# rc13-mbed-main-board2.net
KiCad netlist of a schematic drawn in EAGLE
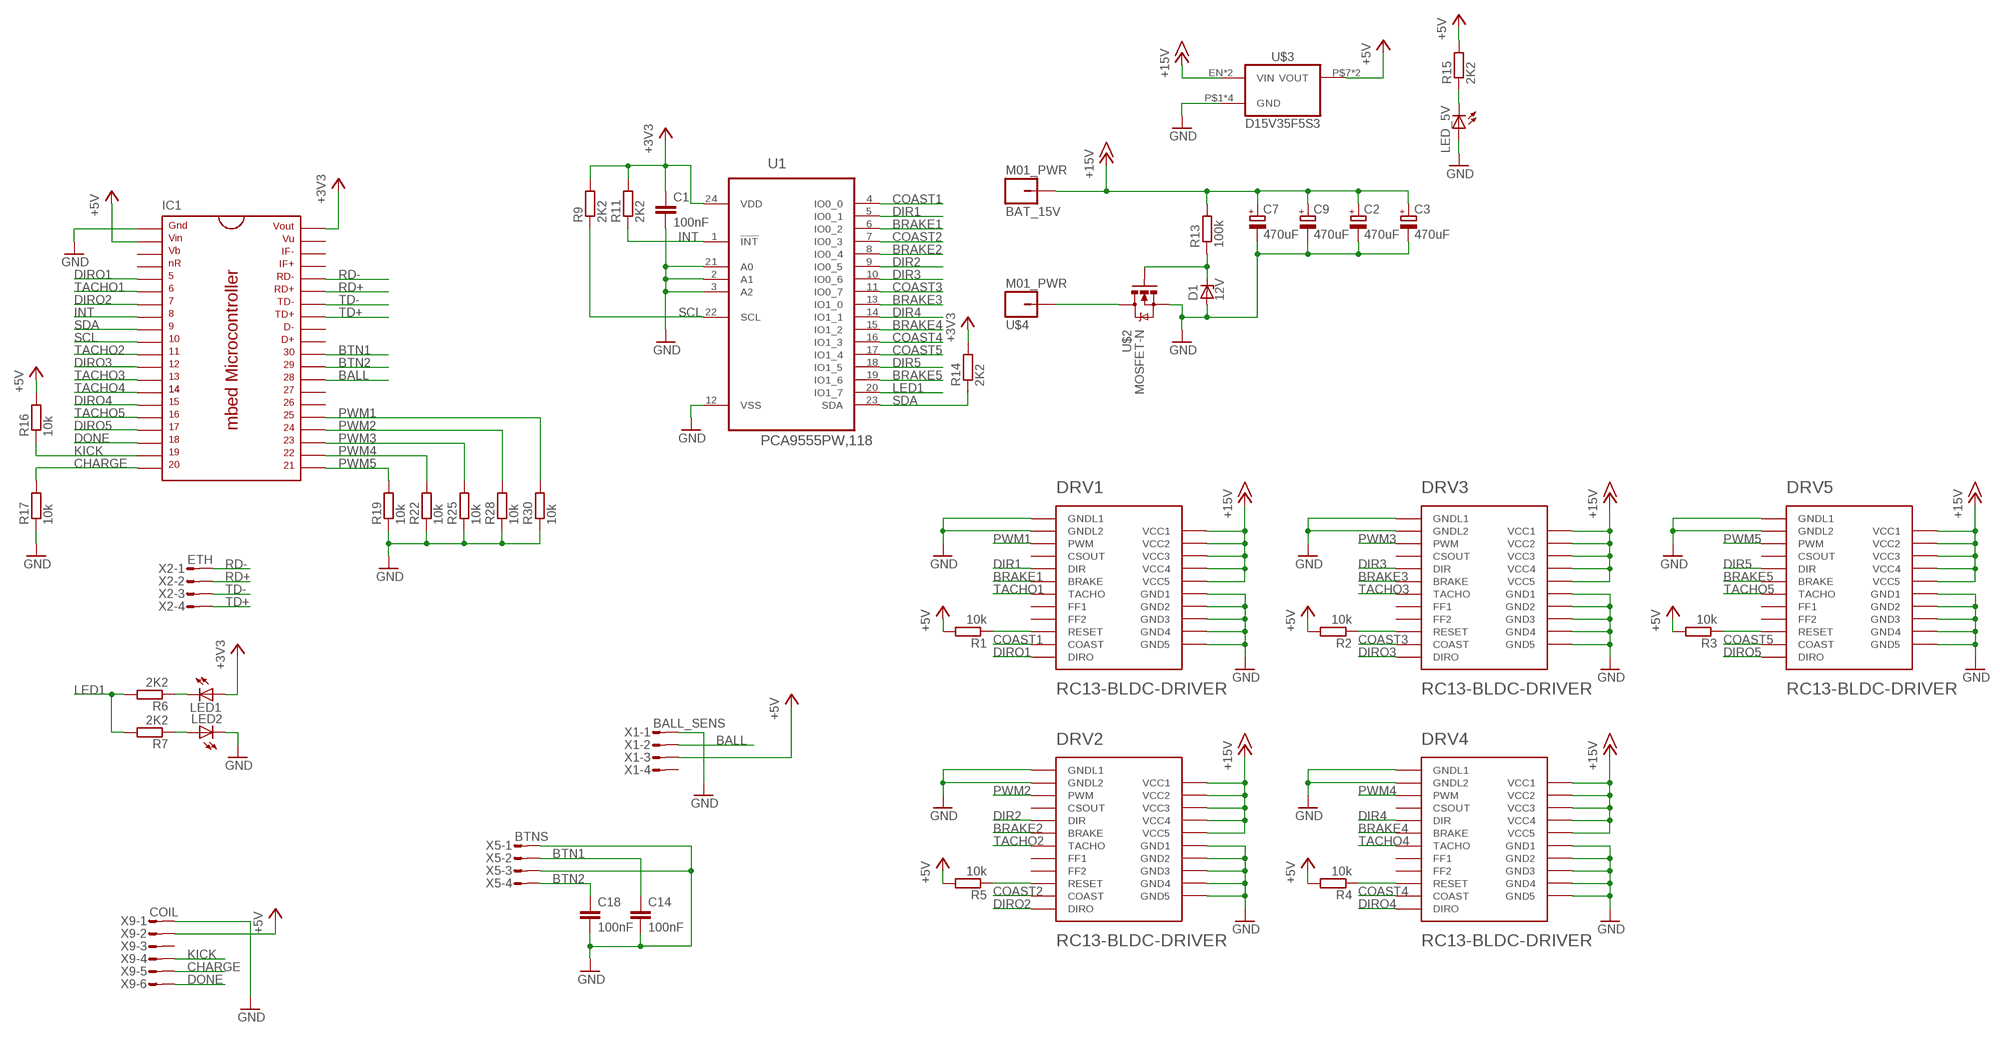
[diagram p0: schematic, sheet 1]

(export (version "E")
  (design (tool "Eeschema 10.0.6"))
  (components
    (comp (ref "BAT_15V")
      (value "M01_PWR")
      (footprint "eagle-import:PWR_HOLE")
      (libsource (lib "eagle-import") (part "M01_PWR"))
    )
    (comp (ref "C1")
      (value "100nF")
      (footprint "eagle-import:C0603K")
      (libsource (lib "eagle-import") (part "C-EUC0603K"))
    )
    (comp (ref "C2")
      (value "470uF")
      (footprint "eagle-import:E3,5-8")
      (libsource (lib "eagle-import") (part "CPOL-EUE3.5-8"))
    )
    (comp (ref "C3")
      (value "470uF")
      (footprint "eagle-import:E3,5-8")
      (libsource (lib "eagle-import") (part "CPOL-EUE3.5-8"))
    )
    (comp (ref "C7")
      (value "470uF")
      (footprint "eagle-import:E3,5-8")
      (libsource (lib "eagle-import") (part "CPOL-EUE3.5-8"))
    )
    (comp (ref "C9")
      (value "470uF")
      (footprint "eagle-import:E3,5-8")
      (libsource (lib "eagle-import") (part "CPOL-EUE3.5-8"))
    )
    (comp (ref "C14")
      (value "100nF")
      (footprint "eagle-import:C0603K")
      (libsource (lib "eagle-import") (part "C-EUC0603K"))
    )
    (comp (ref "C18")
      (value "100nF")
      (footprint "eagle-import:C0603K")
      (libsource (lib "eagle-import") (part "C-EUC0603K"))
    )
    (comp (ref "D1")
      (value "12V")
      (footprint "eagle-import:SOD123")
      (libsource (lib "eagle-import") (part "ZENER-DIODESOD123"))
    )
    (comp (ref "DRV1")
      (value "RC13-BLDC-DRIVER")
      (footprint "eagle-import:RC13-BLDC-DRIVER")
      (libsource (lib "eagle-import") (part "RC13-BLDC-DRIVER"))
    )
    (comp (ref "DRV2")
      (value "RC13-BLDC-DRIVER")
      (footprint "eagle-import:RC13-BLDC-DRIVER")
      (libsource (lib "eagle-import") (part "RC13-BLDC-DRIVER"))
    )
    (comp (ref "DRV3")
      (value "RC13-BLDC-DRIVER")
      (footprint "eagle-import:RC13-BLDC-DRIVER")
      (libsource (lib "eagle-import") (part "RC13-BLDC-DRIVER"))
    )
    (comp (ref "DRV4")
      (value "RC13-BLDC-DRIVER")
      (footprint "eagle-import:RC13-BLDC-DRIVER")
      (libsource (lib "eagle-import") (part "RC13-BLDC-DRIVER"))
    )
    (comp (ref "DRV5")
      (value "RC13-BLDC-DRIVER")
      (footprint "eagle-import:RC13-BLDC-DRIVER")
      (libsource (lib "eagle-import") (part "RC13-BLDC-DRIVER"))
    )
    (comp (ref "IC1")
      (value "MBED_MICROCONTROLLER")
      (footprint "eagle-import:DIL40_0.9")
      (libsource (lib "eagle-import") (part "MBED_MICROCONTROLLER"))
    )
    (comp (ref "LED1")
      (value "LEDCHIP-LED0603")
      (footprint "eagle-import:CHIP-LED0603")
      (libsource (lib "eagle-import") (part "LEDCHIP-LED0603"))
    )
    (comp (ref "LED2")
      (value "LEDCHIP-LED0603")
      (footprint "eagle-import:CHIP-LED0603")
      (libsource (lib "eagle-import") (part "LEDCHIP-LED0603"))
    )
    (comp (ref "LED_5V")
      (value "LEDCHIP-LED0603")
      (footprint "eagle-import:CHIP-LED0603")
      (libsource (lib "eagle-import") (part "LEDCHIP-LED0603"))
    )
    (comp (ref "R1")
      (value "10k")
      (footprint "eagle-import:R0603")
      (libsource (lib "eagle-import") (part "R-EU_R0603"))
    )
    (comp (ref "R2")
      (value "10k")
      (footprint "eagle-import:R0603")
      (libsource (lib "eagle-import") (part "R-EU_R0603"))
    )
    (comp (ref "R3")
      (value "10k")
      (footprint "eagle-import:R0603")
      (libsource (lib "eagle-import") (part "R-EU_R0603"))
    )
    (comp (ref "R4")
      (value "10k")
      (footprint "eagle-import:R0603")
      (libsource (lib "eagle-import") (part "R-EU_R0603"))
    )
    (comp (ref "R5")
      (value "10k")
      (footprint "eagle-import:R0603")
      (libsource (lib "eagle-import") (part "R-EU_R0603"))
    )
    (comp (ref "R6")
      (value "2K2")
      (footprint "eagle-import:R0603")
      (libsource (lib "eagle-import") (part "R-EU_R0603"))
    )
    (comp (ref "R7")
      (value "2K2")
      (footprint "eagle-import:R0603")
      (libsource (lib "eagle-import") (part "R-EU_R0603"))
    )
    (comp (ref "R9")
      (value "2K2")
      (footprint "eagle-import:R0603")
      (libsource (lib "eagle-import") (part "R-EU_R0603"))
    )
    (comp (ref "R11")
      (value "2K2")
      (footprint "eagle-import:R0603")
      (libsource (lib "eagle-import") (part "R-EU_R0603"))
    )
    (comp (ref "R13")
      (value "100k")
      (footprint "eagle-import:R0603")
      (libsource (lib "eagle-import") (part "R-EU_R0603"))
    )
    (comp (ref "R14")
      (value "2K2")
      (footprint "eagle-import:R0603")
      (libsource (lib "eagle-import") (part "R-EU_R0603"))
    )
    (comp (ref "R15")
      (value "2K2")
      (footprint "eagle-import:R0603")
      (libsource (lib "eagle-import") (part "R-EU_R0603"))
    )
    (comp (ref "R16")
      (value "10k")
      (footprint "eagle-import:R0603")
      (libsource (lib "eagle-import") (part "R-EU_R0603"))
    )
    (comp (ref "R17")
      (value "10k")
      (footprint "eagle-import:R0603")
      (libsource (lib "eagle-import") (part "R-EU_R0603"))
    )
    (comp (ref "R19")
      (value "10k")
      (footprint "eagle-import:R0603")
      (libsource (lib "eagle-import") (part "R-EU_R0603"))
    )
    (comp (ref "R22")
      (value "10k")
      (footprint "eagle-import:R0603")
      (libsource (lib "eagle-import") (part "R-EU_R0603"))
    )
    (comp (ref "R25")
      (value "10k")
      (footprint "eagle-import:R0603")
      (libsource (lib "eagle-import") (part "R-EU_R0603"))
    )
    (comp (ref "R28")
      (value "10k")
      (footprint "eagle-import:R0603")
      (libsource (lib "eagle-import") (part "R-EU_R0603"))
    )
    (comp (ref "R30")
      (value "10k")
      (footprint "eagle-import:R0603")
      (libsource (lib "eagle-import") (part "R-EU_R0603"))
    )
    (comp (ref "U$2")
      (value "MOSFET-N")
      (footprint "eagle-import:TO127P600X120-5N")
      (libsource (lib "eagle-import") (part "MOSFET-N-SOT669"))
    )
    (comp (ref "U$3")
      (value "D15V35F5S3")
      (footprint "eagle-import:D15V35F5S3")
      (libsource (lib "eagle-import") (part "D15V35F5S3"))
    )
    (comp (ref "U$4")
      (value "M01_PWR")
      (footprint "eagle-import:PWR_HOLE")
      (libsource (lib "eagle-import") (part "M01_PWR"))
    )
    (comp (ref "U1")
      (value "PCA9555PW,118")
      (footprint "eagle-import:SOP65P640X110-24N")
      (libsource (lib "eagle-import") (part "PCA9555PW,118"))
    )
    (comp (ref "X1")
      (value "BALL_SENS")
      (footprint "eagle-import:MICROMATCH-4")
      (fields (field (name "MPN") "7-215464-4"))
      (libsource (lib "eagle-import") (part "MICROMATCH-4"))
    )
    (comp (ref "X2")
      (value "ETH")
      (footprint "eagle-import:MICROMATCH-4")
      (fields (field (name "MPN") "7-215464-4"))
      (libsource (lib "eagle-import") (part "MICROMATCH-4"))
    )
    (comp (ref "X5")
      (value "BTNS")
      (footprint "eagle-import:MICROMATCH-4")
      (fields (field (name "MPN") "7-215464-4"))
      (libsource (lib "eagle-import") (part "MICROMATCH-4"))
    )
    (comp (ref "X9")
      (value "COIL")
      (footprint "eagle-import:MICROMATCH-6")
      (fields (field (name "MPN") "7-215464-6"))
      (libsource (lib "eagle-import") (part "MICROMATCH-6"))
    )
  )
  (nets
    (net (code "1") (name "+3V3") (class "Default")
      (node (ref "C1") (pin "1") (pinfunction "1_1") (pintype "passive"))
      (node (ref "IC1") (pin "40") (pinfunction "P$40_40") (pintype "bidirectional"))
      (node (ref "LED1") (pin "A") (pinfunction "A_A") (pintype "passive"))
      (node (ref "R11") (pin "2") (pinfunction "2_2") (pintype "passive"))
      (node (ref "R14") (pin "2") (pinfunction "2_2") (pintype "passive"))
      (node (ref "R9") (pin "2") (pinfunction "2_2") (pintype "passive"))
      (node (ref "U1") (pin "24") (pinfunction "VDD_24") (pintype "power_in"))
    )
    (net (code "2") (name "+5V") (class "Default")
      (node (ref "IC1") (pin "2") (pinfunction "P$2_2") (pintype "bidirectional"))
      (node (ref "R1") (pin "2") (pinfunction "2_2") (pintype "passive"))
      (node (ref "R15") (pin "2") (pinfunction "2_2") (pintype "passive"))
      (node (ref "R16") (pin "2") (pinfunction "2_2") (pintype "passive"))
      (node (ref "R2") (pin "2") (pinfunction "2_2") (pintype "passive"))
      (node (ref "R3") (pin "2") (pinfunction "2_2") (pintype "passive"))
      (node (ref "R4") (pin "2") (pinfunction "2_2") (pintype "passive"))
      (node (ref "R5") (pin "2") (pinfunction "2_2") (pintype "passive"))
      (node (ref "U$3") (pin "P$7") (pinfunction "VOUT_P$7") (pintype "power_in"))
      (node (ref "U$3") (pin "P$8") (pinfunction "VOUT_P$8") (pintype "power_in"))
      (node (ref "X1") (pin "3") (pinfunction "S_3") (pintype "passive"))
      (node (ref "X9") (pin "2") (pinfunction "S_2") (pintype "passive"))
    )
    (net (code "3") (name "+15V") (class "Default")
      (node (ref "BAT_15V") (pin "P$1") (pinfunction "P$1_P$1") (pintype "bidirectional"))
      (node (ref "C2") (pin "+") (pinfunction "+_+") (pintype "passive"))
      (node (ref "C3") (pin "+") (pinfunction "+_+") (pintype "passive"))
      (node (ref "C7") (pin "+") (pinfunction "+_+") (pintype "passive"))
      (node (ref "C9") (pin "+") (pinfunction "+_+") (pintype "passive"))
      (node (ref "DRV1") (pin "PWR1") (pinfunction "VCC1_PWR1") (pintype "power_in"))
      (node (ref "DRV1") (pin "PWR2") (pinfunction "VCC2_PWR2") (pintype "power_in"))
      (node (ref "DRV1") (pin "PWR3") (pinfunction "VCC3_PWR3") (pintype "power_in"))
      (node (ref "DRV1") (pin "PWR4") (pinfunction "VCC4_PWR4") (pintype "power_in"))
      (node (ref "DRV1") (pin "PWR5") (pinfunction "VCC5_PWR5") (pintype "power_in"))
      (node (ref "DRV2") (pin "PWR1") (pinfunction "VCC1_PWR1") (pintype "power_in"))
      (node (ref "DRV2") (pin "PWR2") (pinfunction "VCC2_PWR2") (pintype "power_in"))
      (node (ref "DRV2") (pin "PWR3") (pinfunction "VCC3_PWR3") (pintype "power_in"))
      (node (ref "DRV2") (pin "PWR4") (pinfunction "VCC4_PWR4") (pintype "power_in"))
      (node (ref "DRV2") (pin "PWR5") (pinfunction "VCC5_PWR5") (pintype "power_in"))
      (node (ref "DRV3") (pin "PWR1") (pinfunction "VCC1_PWR1") (pintype "power_in"))
      (node (ref "DRV3") (pin "PWR2") (pinfunction "VCC2_PWR2") (pintype "power_in"))
      (node (ref "DRV3") (pin "PWR3") (pinfunction "VCC3_PWR3") (pintype "power_in"))
      (node (ref "DRV3") (pin "PWR4") (pinfunction "VCC4_PWR4") (pintype "power_in"))
      (node (ref "DRV3") (pin "PWR5") (pinfunction "VCC5_PWR5") (pintype "power_in"))
      (node (ref "DRV4") (pin "PWR1") (pinfunction "VCC1_PWR1") (pintype "power_in"))
      (node (ref "DRV4") (pin "PWR2") (pinfunction "VCC2_PWR2") (pintype "power_in"))
      (node (ref "DRV4") (pin "PWR3") (pinfunction "VCC3_PWR3") (pintype "power_in"))
      (node (ref "DRV4") (pin "PWR4") (pinfunction "VCC4_PWR4") (pintype "power_in"))
      (node (ref "DRV4") (pin "PWR5") (pinfunction "VCC5_PWR5") (pintype "power_in"))
      (node (ref "DRV5") (pin "PWR1") (pinfunction "VCC1_PWR1") (pintype "power_in"))
      (node (ref "DRV5") (pin "PWR2") (pinfunction "VCC2_PWR2") (pintype "power_in"))
      (node (ref "DRV5") (pin "PWR3") (pinfunction "VCC3_PWR3") (pintype "power_in"))
      (node (ref "DRV5") (pin "PWR4") (pinfunction "VCC4_PWR4") (pintype "power_in"))
      (node (ref "DRV5") (pin "PWR5") (pinfunction "VCC5_PWR5") (pintype "power_in"))
      (node (ref "R13") (pin "2") (pinfunction "2_2") (pintype "passive"))
      (node (ref "U$3") (pin "EN") (pinfunction "VIN_EN") (pintype "power_in"))
      (node (ref "U$3") (pin "P$5") (pinfunction "VIN_P$5") (pintype "power_in"))
    )
    (net (code "4") (name "/BALL") (class "Default")
      (node (ref "IC1") (pin "28") (pinfunction "P$28_28") (pintype "bidirectional"))
      (node (ref "X1") (pin "2") (pinfunction "S_2") (pintype "passive"))
    )
    (net (code "5") (name "/BRAKE1") (class "Default")
      (node (ref "DRV1") (pin "LOGIC6") (pinfunction "BRAKE_LOGIC6") (pintype "input"))
      (node (ref "U1") (pin "6") (pinfunction "IO0_2_6") (pintype "bidirectional"))
    )
    (net (code "6") (name "/BRAKE2") (class "Default")
      (node (ref "DRV2") (pin "LOGIC6") (pinfunction "BRAKE_LOGIC6") (pintype "input"))
      (node (ref "U1") (pin "8") (pinfunction "IO0_4_8") (pintype "bidirectional"))
    )
    (net (code "7") (name "/BRAKE3") (class "Default")
      (node (ref "DRV3") (pin "LOGIC6") (pinfunction "BRAKE_LOGIC6") (pintype "input"))
      (node (ref "U1") (pin "13") (pinfunction "IO1_0_13") (pintype "bidirectional"))
    )
    (net (code "8") (name "/BRAKE4") (class "Default")
      (node (ref "DRV4") (pin "LOGIC6") (pinfunction "BRAKE_LOGIC6") (pintype "input"))
      (node (ref "U1") (pin "15") (pinfunction "IO1_2_15") (pintype "bidirectional"))
    )
    (net (code "9") (name "/BRAKE5") (class "Default")
      (node (ref "DRV5") (pin "LOGIC6") (pinfunction "BRAKE_LOGIC6") (pintype "input"))
      (node (ref "U1") (pin "19") (pinfunction "IO1_6_19") (pintype "bidirectional"))
    )
    (net (code "10") (name "/BTN1") (class "Default")
      (node (ref "C14") (pin "1") (pinfunction "1_1") (pintype "passive"))
      (node (ref "IC1") (pin "30") (pinfunction "P$30_30") (pintype "bidirectional"))
      (node (ref "X5") (pin "2") (pinfunction "S_2") (pintype "passive"))
    )
    (net (code "11") (name "/BTN2") (class "Default")
      (node (ref "C18") (pin "1") (pinfunction "1_1") (pintype "passive"))
      (node (ref "IC1") (pin "29") (pinfunction "P$29_29") (pintype "bidirectional"))
      (node (ref "X5") (pin "4") (pinfunction "S_4") (pintype "passive"))
    )
    (net (code "12") (name "/CHARGE") (class "Default")
      (node (ref "IC1") (pin "20") (pinfunction "P$20_20") (pintype "bidirectional"))
      (node (ref "R17") (pin "2") (pinfunction "2_2") (pintype "passive"))
      (node (ref "X9") (pin "5") (pinfunction "S_5") (pintype "passive"))
    )
    (net (code "13") (name "/COAST1") (class "Default")
      (node (ref "DRV1") (pin "LOGIC11") (pinfunction "COAST_LOGIC11") (pintype "input"))
      (node (ref "U1") (pin "4") (pinfunction "IO0_0_4") (pintype "bidirectional"))
    )
    (net (code "14") (name "/COAST2") (class "Default")
      (node (ref "DRV2") (pin "LOGIC11") (pinfunction "COAST_LOGIC11") (pintype "input"))
      (node (ref "U1") (pin "7") (pinfunction "IO0_3_7") (pintype "bidirectional"))
    )
    (net (code "15") (name "/COAST3") (class "Default")
      (node (ref "DRV3") (pin "LOGIC11") (pinfunction "COAST_LOGIC11") (pintype "input"))
      (node (ref "U1") (pin "11") (pinfunction "IO0_7_11") (pintype "bidirectional"))
    )
    (net (code "16") (name "/COAST4") (class "Default")
      (node (ref "DRV4") (pin "LOGIC11") (pinfunction "COAST_LOGIC11") (pintype "input"))
      (node (ref "U1") (pin "16") (pinfunction "IO1_3_16") (pintype "bidirectional"))
    )
    (net (code "17") (name "/COAST5") (class "Default")
      (node (ref "DRV5") (pin "LOGIC11") (pinfunction "COAST_LOGIC11") (pintype "input"))
      (node (ref "U1") (pin "17") (pinfunction "IO1_4_17") (pintype "bidirectional"))
    )
    (net (code "18") (name "/DIR1") (class "Default")
      (node (ref "DRV1") (pin "LOGIC5") (pinfunction "DIR_LOGIC5") (pintype "input"))
      (node (ref "U1") (pin "5") (pinfunction "IO0_1_5") (pintype "bidirectional"))
    )
    (net (code "19") (name "/DIR2") (class "Default")
      (node (ref "DRV2") (pin "LOGIC5") (pinfunction "DIR_LOGIC5") (pintype "input"))
      (node (ref "U1") (pin "9") (pinfunction "IO0_5_9") (pintype "bidirectional"))
    )
    (net (code "20") (name "/DIR3") (class "Default")
      (node (ref "DRV3") (pin "LOGIC5") (pinfunction "DIR_LOGIC5") (pintype "input"))
      (node (ref "U1") (pin "10") (pinfunction "IO0_6_10") (pintype "bidirectional"))
    )
    (net (code "21") (name "/DIR4") (class "Default")
      (node (ref "DRV4") (pin "LOGIC5") (pinfunction "DIR_LOGIC5") (pintype "input"))
      (node (ref "U1") (pin "14") (pinfunction "IO1_1_14") (pintype "bidirectional"))
    )
    (net (code "22") (name "/DIR5") (class "Default")
      (node (ref "DRV5") (pin "LOGIC5") (pinfunction "DIR_LOGIC5") (pintype "input"))
      (node (ref "U1") (pin "18") (pinfunction "IO1_5_18") (pintype "bidirectional"))
    )
    (net (code "23") (name "/DIRO1") (class "Default")
      (node (ref "DRV1") (pin "LOGIC12") (pinfunction "DIRO_LOGIC12") (pintype "output"))
      (node (ref "IC1") (pin "5") (pinfunction "P$5_5") (pintype "bidirectional"))
    )
    (net (code "24") (name "/DIRO2") (class "Default")
      (node (ref "DRV2") (pin "LOGIC12") (pinfunction "DIRO_LOGIC12") (pintype "output"))
      (node (ref "IC1") (pin "7") (pinfunction "P$7_7") (pintype "bidirectional"))
    )
    (net (code "25") (name "/DIRO3") (class "Default")
      (node (ref "DRV3") (pin "LOGIC12") (pinfunction "DIRO_LOGIC12") (pintype "output"))
      (node (ref "IC1") (pin "12") (pinfunction "P$12_12") (pintype "bidirectional"))
    )
    (net (code "26") (name "/DIRO4") (class "Default")
      (node (ref "DRV4") (pin "LOGIC12") (pinfunction "DIRO_LOGIC12") (pintype "output"))
      (node (ref "IC1") (pin "15") (pinfunction "P$15_15") (pintype "bidirectional"))
    )
    (net (code "27") (name "/DIRO5") (class "Default")
      (node (ref "DRV5") (pin "LOGIC12") (pinfunction "DIRO_LOGIC12") (pintype "output"))
      (node (ref "IC1") (pin "17") (pinfunction "P$17_17") (pintype "bidirectional"))
    )
    (net (code "28") (name "/DONE") (class "Default")
      (node (ref "IC1") (pin "18") (pinfunction "P$18_18") (pintype "bidirectional"))
      (node (ref "X9") (pin "6") (pinfunction "S_6") (pintype "passive"))
    )
    (net (code "29") (name "/INT") (class "Default")
      (node (ref "IC1") (pin "8") (pinfunction "P$8_8") (pintype "bidirectional"))
      (node (ref "R11") (pin "1") (pinfunction "1_1") (pintype "passive"))
      (node (ref "U1") (pin "1") (pinfunction "~{INT}_1") (pintype "output"))
    )
    (net (code "30") (name "/KICK") (class "Default")
      (node (ref "IC1") (pin "19") (pinfunction "P$19_19") (pintype "bidirectional"))
      (node (ref "R16") (pin "1") (pinfunction "1_1") (pintype "passive"))
      (node (ref "X9") (pin "4") (pinfunction "S_4") (pintype "passive"))
    )
    (net (code "31") (name "/LED1") (class "Default")
      (node (ref "R6") (pin "2") (pinfunction "2_2") (pintype "passive"))
      (node (ref "R7") (pin "2") (pinfunction "2_2") (pintype "passive"))
      (node (ref "U1") (pin "20") (pinfunction "IO1_7_20") (pintype "bidirectional"))
    )
    (net (code "32") (name "/PWM1") (class "Default")
      (node (ref "DRV1") (pin "LOGIC3") (pinfunction "PWM_LOGIC3") (pintype "input"))
      (node (ref "IC1") (pin "25") (pinfunction "P$25_25") (pintype "bidirectional"))
      (node (ref "R30") (pin "2") (pinfunction "2_2") (pintype "passive"))
    )
    (net (code "33") (name "/PWM2") (class "Default")
      (node (ref "DRV2") (pin "LOGIC3") (pinfunction "PWM_LOGIC3") (pintype "input"))
      (node (ref "IC1") (pin "24") (pinfunction "P$24_24") (pintype "bidirectional"))
      (node (ref "R28") (pin "2") (pinfunction "2_2") (pintype "passive"))
    )
    (net (code "34") (name "/PWM3") (class "Default")
      (node (ref "DRV3") (pin "LOGIC3") (pinfunction "PWM_LOGIC3") (pintype "input"))
      (node (ref "IC1") (pin "23") (pinfunction "P$23_23") (pintype "bidirectional"))
      (node (ref "R25") (pin "2") (pinfunction "2_2") (pintype "passive"))
    )
    (net (code "35") (name "/PWM4") (class "Default")
      (node (ref "DRV4") (pin "LOGIC3") (pinfunction "PWM_LOGIC3") (pintype "input"))
      (node (ref "IC1") (pin "22") (pinfunction "P$22_22") (pintype "bidirectional"))
      (node (ref "R22") (pin "2") (pinfunction "2_2") (pintype "passive"))
    )
    (net (code "36") (name "/PWM5") (class "Default")
      (node (ref "DRV5") (pin "LOGIC3") (pinfunction "PWM_LOGIC3") (pintype "input"))
      (node (ref "IC1") (pin "21") (pinfunction "P$21_21") (pintype "bidirectional"))
      (node (ref "R19") (pin "2") (pinfunction "2_2") (pintype "passive"))
    )
    (net (code "37") (name "/RD+") (class "Default")
      (node (ref "IC1") (pin "35") (pinfunction "P$35_35") (pintype "bidirectional"))
      (node (ref "X2") (pin "2") (pinfunction "S_2") (pintype "passive"))
    )
    (net (code "38") (name "/RD-") (class "Default")
      (node (ref "IC1") (pin "36") (pinfunction "P$36_36") (pintype "bidirectional"))
      (node (ref "X2") (pin "1") (pinfunction "S_1") (pintype "passive"))
    )
    (net (code "39") (name "/SCL") (class "Default")
      (node (ref "IC1") (pin "10") (pinfunction "P$10_10") (pintype "bidirectional"))
      (node (ref "R9") (pin "1") (pinfunction "1_1") (pintype "passive"))
      (node (ref "U1") (pin "22") (pinfunction "SCL_22") (pintype "input"))
    )
    (net (code "40") (name "/SDA") (class "Default")
      (node (ref "IC1") (pin "9") (pinfunction "P$9_9") (pintype "bidirectional"))
      (node (ref "R14") (pin "1") (pinfunction "1_1") (pintype "passive"))
      (node (ref "U1") (pin "23") (pinfunction "SDA_23") (pintype "bidirectional"))
    )
    (net (code "41") (name "/TACHO1") (class "Default")
      (node (ref "DRV1") (pin "LOGIC7") (pinfunction "TACHO_LOGIC7") (pintype "output"))
      (node (ref "IC1") (pin "6") (pinfunction "P$6_6") (pintype "bidirectional"))
    )
    (net (code "42") (name "/TACHO2") (class "Default")
      (node (ref "DRV2") (pin "LOGIC7") (pinfunction "TACHO_LOGIC7") (pintype "output"))
      (node (ref "IC1") (pin "11") (pinfunction "P$11_11") (pintype "bidirectional"))
    )
    (net (code "43") (name "/TACHO3") (class "Default")
      (node (ref "DRV3") (pin "LOGIC7") (pinfunction "TACHO_LOGIC7") (pintype "output"))
      (node (ref "IC1") (pin "13") (pinfunction "P$13_13") (pintype "bidirectional"))
    )
    (net (code "44") (name "/TACHO4") (class "Default")
      (node (ref "DRV4") (pin "LOGIC7") (pinfunction "TACHO_LOGIC7") (pintype "output"))
      (node (ref "IC1") (pin "14") (pinfunction "P$14_14") (pintype "bidirectional"))
    )
    (net (code "45") (name "/TACHO5") (class "Default")
      (node (ref "DRV5") (pin "LOGIC7") (pinfunction "TACHO_LOGIC7") (pintype "output"))
      (node (ref "IC1") (pin "16") (pinfunction "P$16_16") (pintype "bidirectional"))
    )
    (net (code "46") (name "/TD+") (class "Default")
      (node (ref "IC1") (pin "33") (pinfunction "P$33_33") (pintype "bidirectional"))
      (node (ref "X2") (pin "4") (pinfunction "S_4") (pintype "passive"))
    )
    (net (code "47") (name "/TD-") (class "Default")
      (node (ref "IC1") (pin "34") (pinfunction "P$34_34") (pintype "bidirectional"))
      (node (ref "X2") (pin "3") (pinfunction "S_3") (pintype "passive"))
    )
    (net (code "48") (name "GND") (class "Default")
      (node (ref "C1") (pin "2") (pinfunction "2_2") (pintype "passive"))
      (node (ref "C14") (pin "2") (pinfunction "2_2") (pintype "passive"))
      (node (ref "C18") (pin "2") (pinfunction "2_2") (pintype "passive"))
      (node (ref "C2") (pin "-") (pinfunction "-_-") (pintype "passive"))
      (node (ref "C3") (pin "-") (pinfunction "-_-") (pintype "passive"))
      (node (ref "C7") (pin "-") (pinfunction "-_-") (pintype "passive"))
      (node (ref "C9") (pin "-") (pinfunction "-_-") (pintype "passive"))
      (node (ref "D1") (pin "A") (pinfunction "A_A") (pintype "passive"))
      (node (ref "DRV1") (pin "LOGIC1") (pinfunction "GNDL1_LOGIC1") (pintype "power_in"))
      (node (ref "DRV1") (pin "LOGIC2") (pinfunction "GNDL2_LOGIC2") (pintype "power_in"))
      (node (ref "DRV1") (pin "PWR10") (pinfunction "GND5_PWR10") (pintype "power_in"))
      (node (ref "DRV1") (pin "PWR6") (pinfunction "GND1_PWR6") (pintype "power_in"))
      (node (ref "DRV1") (pin "PWR7") (pinfunction "GND2_PWR7") (pintype "power_in"))
      (node (ref "DRV1") (pin "PWR8") (pinfunction "GND3_PWR8") (pintype "power_in"))
      (node (ref "DRV1") (pin "PWR9") (pinfunction "GND4_PWR9") (pintype "power_in"))
      (node (ref "DRV2") (pin "LOGIC1") (pinfunction "GNDL1_LOGIC1") (pintype "power_in"))
      (node (ref "DRV2") (pin "LOGIC2") (pinfunction "GNDL2_LOGIC2") (pintype "power_in"))
      (node (ref "DRV2") (pin "PWR10") (pinfunction "GND5_PWR10") (pintype "power_in"))
      (node (ref "DRV2") (pin "PWR6") (pinfunction "GND1_PWR6") (pintype "power_in"))
      (node (ref "DRV2") (pin "PWR7") (pinfunction "GND2_PWR7") (pintype "power_in"))
      (node (ref "DRV2") (pin "PWR8") (pinfunction "GND3_PWR8") (pintype "power_in"))
      (node (ref "DRV2") (pin "PWR9") (pinfunction "GND4_PWR9") (pintype "power_in"))
      (node (ref "DRV3") (pin "LOGIC1") (pinfunction "GNDL1_LOGIC1") (pintype "power_in"))
      (node (ref "DRV3") (pin "LOGIC2") (pinfunction "GNDL2_LOGIC2") (pintype "power_in"))
      (node (ref "DRV3") (pin "PWR10") (pinfunction "GND5_PWR10") (pintype "power_in"))
      (node (ref "DRV3") (pin "PWR6") (pinfunction "GND1_PWR6") (pintype "power_in"))
      (node (ref "DRV3") (pin "PWR7") (pinfunction "GND2_PWR7") (pintype "power_in"))
      (node (ref "DRV3") (pin "PWR8") (pinfunction "GND3_PWR8") (pintype "power_in"))
      (node (ref "DRV3") (pin "PWR9") (pinfunction "GND4_PWR9") (pintype "power_in"))
      (node (ref "DRV4") (pin "LOGIC1") (pinfunction "GNDL1_LOGIC1") (pintype "power_in"))
      (node (ref "DRV4") (pin "LOGIC2") (pinfunction "GNDL2_LOGIC2") (pintype "power_in"))
      (node (ref "DRV4") (pin "PWR10") (pinfunction "GND5_PWR10") (pintype "power_in"))
      (node (ref "DRV4") (pin "PWR6") (pinfunction "GND1_PWR6") (pintype "power_in"))
      (node (ref "DRV4") (pin "PWR7") (pinfunction "GND2_PWR7") (pintype "power_in"))
      (node (ref "DRV4") (pin "PWR8") (pinfunction "GND3_PWR8") (pintype "power_in"))
      (node (ref "DRV4") (pin "PWR9") (pinfunction "GND4_PWR9") (pintype "power_in"))
      (node (ref "DRV5") (pin "LOGIC1") (pinfunction "GNDL1_LOGIC1") (pintype "power_in"))
      (node (ref "DRV5") (pin "LOGIC2") (pinfunction "GNDL2_LOGIC2") (pintype "power_in"))
      (node (ref "DRV5") (pin "PWR10") (pinfunction "GND5_PWR10") (pintype "power_in"))
      (node (ref "DRV5") (pin "PWR6") (pinfunction "GND1_PWR6") (pintype "power_in"))
      (node (ref "DRV5") (pin "PWR7") (pinfunction "GND2_PWR7") (pintype "power_in"))
      (node (ref "DRV5") (pin "PWR8") (pinfunction "GND3_PWR8") (pintype "power_in"))
      (node (ref "DRV5") (pin "PWR9") (pinfunction "GND4_PWR9") (pintype "power_in"))
      (node (ref "IC1") (pin "1") (pinfunction "P$1_1") (pintype "bidirectional"))
      (node (ref "LED2") (pin "C") (pinfunction "C_C") (pintype "passive"))
      (node (ref "LED_5V") (pin "A") (pinfunction "A_A") (pintype "passive"))
      (node (ref "R17") (pin "1") (pinfunction "1_1") (pintype "passive"))
      (node (ref "R19") (pin "1") (pinfunction "1_1") (pintype "passive"))
      (node (ref "R22") (pin "1") (pinfunction "1_1") (pintype "passive"))
      (node (ref "R25") (pin "1") (pinfunction "1_1") (pintype "passive"))
      (node (ref "R28") (pin "1") (pinfunction "1_1") (pintype "passive"))
      (node (ref "R30") (pin "1") (pinfunction "1_1") (pintype "passive"))
      (node (ref "U$2") (pin "1") (pinfunction "S_1") (pintype "passive"))
      (node (ref "U$2") (pin "2") (pinfunction "S_2") (pintype "passive"))
      (node (ref "U$2") (pin "3") (pinfunction "S_3") (pintype "passive"))
      (node (ref "U$3") (pin "P$1") (pinfunction "GND_P$1") (pintype "power_in"))
      (node (ref "U$3") (pin "P$2") (pinfunction "GND_P$2") (pintype "power_in"))
      (node (ref "U$3") (pin "P$3") (pinfunction "GND_P$3") (pintype "power_in"))
      (node (ref "U$3") (pin "P$4") (pinfunction "GND_P$4") (pintype "power_in"))
      (node (ref "U1") (pin "12") (pinfunction "VSS_12") (pintype "power_in"))
      (node (ref "U1") (pin "2") (pinfunction "A1_2") (pintype "input"))
      (node (ref "U1") (pin "21") (pinfunction "A0_21") (pintype "input"))
      (node (ref "U1") (pin "3") (pinfunction "A2_3") (pintype "input"))
      (node (ref "X1") (pin "1") (pinfunction "S_1") (pintype "passive"))
      (node (ref "X5") (pin "1") (pinfunction "S_1") (pintype "passive"))
      (node (ref "X5") (pin "3") (pinfunction "S_3") (pintype "passive"))
      (node (ref "X9") (pin "1") (pinfunction "S_1") (pintype "passive"))
    )
    (net (code "49") (name "Net-(DRV1-RESET)") (class "Default")
      (node (ref "DRV1") (pin "LOGIC10") (pinfunction "RESET_LOGIC10") (pintype "input"))
      (node (ref "R1") (pin "1") (pinfunction "1_1") (pintype "passive"))
    )
    (net (code "50") (name "Net-(DRV2-RESET)") (class "Default")
      (node (ref "DRV2") (pin "LOGIC10") (pinfunction "RESET_LOGIC10") (pintype "input"))
      (node (ref "R5") (pin "1") (pinfunction "1_1") (pintype "passive"))
    )
    (net (code "51") (name "Net-(DRV3-RESET)") (class "Default")
      (node (ref "DRV3") (pin "LOGIC10") (pinfunction "RESET_LOGIC10") (pintype "input"))
      (node (ref "R2") (pin "1") (pinfunction "1_1") (pintype "passive"))
    )
    (net (code "52") (name "Net-(DRV4-RESET)") (class "Default")
      (node (ref "DRV4") (pin "LOGIC10") (pinfunction "RESET_LOGIC10") (pintype "input"))
      (node (ref "R4") (pin "1") (pinfunction "1_1") (pintype "passive"))
    )
    (net (code "53") (name "Net-(DRV5-RESET)") (class "Default")
      (node (ref "DRV5") (pin "LOGIC10") (pinfunction "RESET_LOGIC10") (pintype "input"))
      (node (ref "R3") (pin "1") (pinfunction "1_1") (pintype "passive"))
    )
    (net (code "54") (name "Net-(LED1-PadC)") (class "Default")
      (node (ref "LED1") (pin "C") (pinfunction "C_C") (pintype "passive"))
      (node (ref "R6") (pin "1") (pinfunction "1_1") (pintype "passive"))
    )
    (net (code "55") (name "Net-(LED2-PadA)") (class "Default")
      (node (ref "LED2") (pin "A") (pinfunction "A_A") (pintype "passive"))
      (node (ref "R7") (pin "1") (pinfunction "1_1") (pintype "passive"))
    )
    (net (code "56") (name "Net-(LED_5V-PadC)") (class "Default")
      (node (ref "LED_5V") (pin "C") (pinfunction "C_C") (pintype "passive"))
      (node (ref "R15") (pin "1") (pinfunction "1_1") (pintype "passive"))
    )
    (net (code "57") (name "Net-(U$2-D)") (class "Default")
      (node (ref "U$2") (pin "5") (pinfunction "D_5") (pintype "passive"))
      (node (ref "U$4") (pin "P$1") (pinfunction "P$1_P$1") (pintype "bidirectional"))
    )
    (net (code "58") (name "Net-(U$2-G)") (class "Default")
      (node (ref "D1") (pin "C") (pinfunction "C_C") (pintype "passive"))
      (node (ref "R13") (pin "1") (pinfunction "1_1") (pintype "passive"))
      (node (ref "U$2") (pin "4") (pinfunction "G_4") (pintype "passive"))
    )
    (net (code "59") (name "unconnected-(DRV1-CSOUT-PadLOGIC4)") (class "Default")
      (node (ref "DRV1") (pin "LOGIC4") (pinfunction "CSOUT_LOGIC4") (pintype "output"))
    )
    (net (code "60") (name "unconnected-(DRV1-FF1-PadLOGIC8)") (class "Default")
      (node (ref "DRV1") (pin "LOGIC8") (pinfunction "FF1_LOGIC8") (pintype "output"))
    )
    (net (code "61") (name "unconnected-(DRV1-FF2-PadLOGIC9)") (class "Default")
      (node (ref "DRV1") (pin "LOGIC9") (pinfunction "FF2_LOGIC9") (pintype "output"))
    )
    (net (code "62") (name "unconnected-(DRV2-CSOUT-PadLOGIC4)") (class "Default")
      (node (ref "DRV2") (pin "LOGIC4") (pinfunction "CSOUT_LOGIC4") (pintype "output"))
    )
    (net (code "63") (name "unconnected-(DRV2-FF1-PadLOGIC8)") (class "Default")
      (node (ref "DRV2") (pin "LOGIC8") (pinfunction "FF1_LOGIC8") (pintype "output"))
    )
    (net (code "64") (name "unconnected-(DRV2-FF2-PadLOGIC9)") (class "Default")
      (node (ref "DRV2") (pin "LOGIC9") (pinfunction "FF2_LOGIC9") (pintype "output"))
    )
    (net (code "65") (name "unconnected-(DRV3-CSOUT-PadLOGIC4)") (class "Default")
      (node (ref "DRV3") (pin "LOGIC4") (pinfunction "CSOUT_LOGIC4") (pintype "output"))
    )
    (net (code "66") (name "unconnected-(DRV3-FF1-PadLOGIC8)") (class "Default")
      (node (ref "DRV3") (pin "LOGIC8") (pinfunction "FF1_LOGIC8") (pintype "output"))
    )
    (net (code "67") (name "unconnected-(DRV3-FF2-PadLOGIC9)") (class "Default")
      (node (ref "DRV3") (pin "LOGIC9") (pinfunction "FF2_LOGIC9") (pintype "output"))
    )
    (net (code "68") (name "unconnected-(DRV4-CSOUT-PadLOGIC4)") (class "Default")
      (node (ref "DRV4") (pin "LOGIC4") (pinfunction "CSOUT_LOGIC4") (pintype "output"))
    )
    (net (code "69") (name "unconnected-(DRV4-FF1-PadLOGIC8)") (class "Default")
      (node (ref "DRV4") (pin "LOGIC8") (pinfunction "FF1_LOGIC8") (pintype "output"))
    )
    (net (code "70") (name "unconnected-(DRV4-FF2-PadLOGIC9)") (class "Default")
      (node (ref "DRV4") (pin "LOGIC9") (pinfunction "FF2_LOGIC9") (pintype "output"))
    )
    (net (code "71") (name "unconnected-(DRV5-CSOUT-PadLOGIC4)") (class "Default")
      (node (ref "DRV5") (pin "LOGIC4") (pinfunction "CSOUT_LOGIC4") (pintype "output"))
    )
    (net (code "72") (name "unconnected-(DRV5-FF1-PadLOGIC8)") (class "Default")
      (node (ref "DRV5") (pin "LOGIC8") (pinfunction "FF1_LOGIC8") (pintype "output"))
    )
    (net (code "73") (name "unconnected-(DRV5-FF2-PadLOGIC9)") (class "Default")
      (node (ref "DRV5") (pin "LOGIC9") (pinfunction "FF2_LOGIC9") (pintype "output"))
    )
    (net (code "74") (name "unconnected-(IC1-P$3-Pad3)") (class "Default")
      (node (ref "IC1") (pin "3") (pinfunction "P$3_3") (pintype "bidirectional"))
    )
    (net (code "75") (name "unconnected-(IC1-P$4-Pad4)") (class "Default")
      (node (ref "IC1") (pin "4") (pinfunction "P$4_4") (pintype "bidirectional"))
    )
    (net (code "76") (name "unconnected-(IC1-P$26-Pad26)") (class "Default")
      (node (ref "IC1") (pin "26") (pinfunction "P$26_26") (pintype "bidirectional"))
    )
    (net (code "77") (name "unconnected-(IC1-P$27-Pad27)") (class "Default")
      (node (ref "IC1") (pin "27") (pinfunction "P$27_27") (pintype "bidirectional"))
    )
    (net (code "78") (name "unconnected-(IC1-P$31-Pad31)") (class "Default")
      (node (ref "IC1") (pin "31") (pinfunction "P$31_31") (pintype "bidirectional"))
    )
    (net (code "79") (name "unconnected-(IC1-P$32-Pad32)") (class "Default")
      (node (ref "IC1") (pin "32") (pinfunction "P$32_32") (pintype "bidirectional"))
    )
    (net (code "80") (name "unconnected-(IC1-P$37-Pad37)") (class "Default")
      (node (ref "IC1") (pin "37") (pinfunction "P$37_37") (pintype "bidirectional"))
    )
    (net (code "81") (name "unconnected-(IC1-P$38-Pad38)") (class "Default")
      (node (ref "IC1") (pin "38") (pinfunction "P$38_38") (pintype "bidirectional"))
    )
    (net (code "82") (name "unconnected-(IC1-P$39-Pad39)") (class "Default")
      (node (ref "IC1") (pin "39") (pinfunction "P$39_39") (pintype "bidirectional"))
    )
    (net (code "83") (name "unconnected-(X1D-S-Pad4)") (class "Default")
      (node (ref "X1") (pin "4") (pinfunction "S_4") (pintype "passive"))
    )
    (net (code "84") (name "unconnected-(X9C-S-Pad3)") (class "Default")
      (node (ref "X9") (pin "3") (pinfunction "S_3") (pintype "passive"))
    )
  )
)
